# ATmega328P_MCU.net
KiCad netlist of a schematic drawn in EAGLE
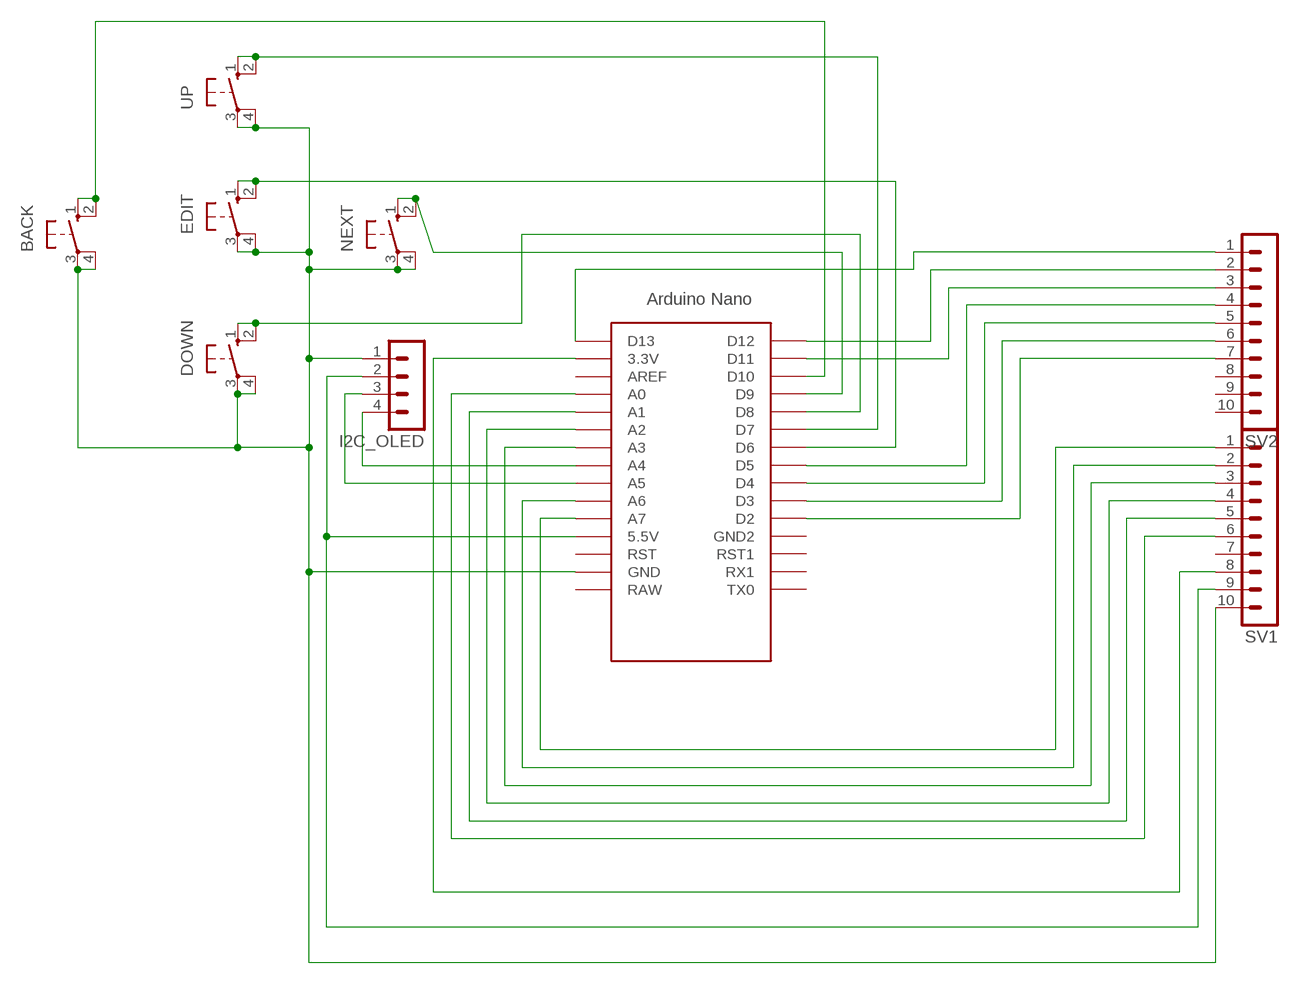
[diagram p0: schematic, sheet 1]

(export (version "E")
  (design (tool "Eeschema 10.0.6"))
  (components
    (comp (ref "ARDUINO")
      (value "NANO")
      (footprint "eagle-import:NANO")
      (libsource (lib "eagle-import") (part "NANO"))
    )
    (comp (ref "BACK")
      (value "10-XX")
      (footprint "eagle-import:B3F-10XX")
      (fields (field (name "MPN") "B3F-1000"))
      (libsource (lib "eagle-import") (part "10-XX"))
    )
    (comp (ref "DOWN")
      (value "10-XX")
      (footprint "eagle-import:B3F-10XX")
      (fields (field (name "MPN") "B3F-1000"))
      (libsource (lib "eagle-import") (part "10-XX"))
    )
    (comp (ref "EDIT")
      (value "10-XX")
      (footprint "eagle-import:B3F-10XX")
      (fields (field (name "MPN") "B3F-1000"))
      (libsource (lib "eagle-import") (part "10-XX"))
    )
    (comp (ref "I2C_OLED")
      (value "MA04-1")
      (footprint "eagle-import:MA04-1")
      (libsource (lib "eagle-import") (part "MA04-1"))
    )
    (comp (ref "NEXT")
      (value "10-XX")
      (footprint "eagle-import:B3F-10XX")
      (fields (field (name "MPN") "B3F-1000"))
      (libsource (lib "eagle-import") (part "10-XX"))
    )
    (comp (ref "SV1")
      (value "MA10-1")
      (footprint "eagle-import:MA10-1")
      (libsource (lib "eagle-import") (part "MA10-1"))
    )
    (comp (ref "SV2")
      (value "MA10-1")
      (footprint "eagle-import:MA10-1")
      (libsource (lib "eagle-import") (part "MA10-1"))
    )
    (comp (ref "UP")
      (value "10-XX")
      (footprint "eagle-import:B3F-10XX")
      (fields (field (name "MPN") "B3F-1000"))
      (libsource (lib "eagle-import") (part "10-XX"))
    )
  )
  (nets
    (net (code "1") (name "Net-(ARDUINO-5.5V)") (class "Default")
      (node (ref "ARDUINO") (pin "5V") (pinfunction "5.5V_5V") (pintype "bidirectional"))
      (node (ref "I2C_OLED") (pin "2") (pinfunction "2_2") (pintype "passive"))
      (node (ref "SV1") (pin "9") (pinfunction "9_9") (pintype "passive"))
    )
    (net (code "2") (name "Net-(ARDUINO-Pad3.3V)") (class "Default")
      (node (ref "ARDUINO") (pin "3.3V") (pinfunction "3.3V_3.3V") (pintype "bidirectional"))
      (node (ref "SV1") (pin "8") (pinfunction "8_8") (pintype "passive"))
    )
    (net (code "3") (name "Net-(ARDUINO-PadA0)") (class "Default")
      (node (ref "ARDUINO") (pin "A0") (pinfunction "A0_A0") (pintype "bidirectional"))
      (node (ref "SV1") (pin "6") (pinfunction "6_6") (pintype "passive"))
    )
    (net (code "4") (name "Net-(ARDUINO-PadA1)") (class "Default")
      (node (ref "ARDUINO") (pin "A1") (pinfunction "A1_A1") (pintype "bidirectional"))
      (node (ref "SV1") (pin "5") (pinfunction "5_5") (pintype "passive"))
    )
    (net (code "5") (name "Net-(ARDUINO-PadA2)") (class "Default")
      (node (ref "ARDUINO") (pin "A2") (pinfunction "A2_A2") (pintype "bidirectional"))
      (node (ref "SV1") (pin "4") (pinfunction "4_4") (pintype "passive"))
    )
    (net (code "6") (name "Net-(ARDUINO-PadA3)") (class "Default")
      (node (ref "ARDUINO") (pin "A3") (pinfunction "A3_A3") (pintype "bidirectional"))
      (node (ref "SV1") (pin "3") (pinfunction "3_3") (pintype "passive"))
    )
    (net (code "7") (name "Net-(ARDUINO-PadA4)") (class "Default")
      (node (ref "ARDUINO") (pin "A4") (pinfunction "A4_A4") (pintype "bidirectional"))
      (node (ref "I2C_OLED") (pin "4") (pinfunction "4_4") (pintype "passive"))
    )
    (net (code "8") (name "Net-(ARDUINO-PadA5)") (class "Default")
      (node (ref "ARDUINO") (pin "A5") (pinfunction "A5_A5") (pintype "bidirectional"))
      (node (ref "I2C_OLED") (pin "3") (pinfunction "3_3") (pintype "passive"))
    )
    (net (code "9") (name "Net-(ARDUINO-PadA6)") (class "Default")
      (node (ref "ARDUINO") (pin "A6") (pinfunction "A6_A6") (pintype "bidirectional"))
      (node (ref "SV1") (pin "2") (pinfunction "2_2") (pintype "passive"))
    )
    (net (code "10") (name "Net-(ARDUINO-PadA7)") (class "Default")
      (node (ref "ARDUINO") (pin "A7") (pinfunction "A7_A7") (pintype "bidirectional"))
      (node (ref "SV1") (pin "1") (pinfunction "1_1") (pintype "passive"))
    )
    (net (code "11") (name "Net-(ARDUINO-PadD2)") (class "Default")
      (node (ref "ARDUINO") (pin "D2") (pinfunction "D2_D2") (pintype "bidirectional"))
      (node (ref "SV2") (pin "7") (pinfunction "7_7") (pintype "passive"))
    )
    (net (code "12") (name "Net-(ARDUINO-PadD3)") (class "Default")
      (node (ref "ARDUINO") (pin "D3") (pinfunction "D3_D3") (pintype "bidirectional"))
      (node (ref "SV2") (pin "6") (pinfunction "6_6") (pintype "passive"))
    )
    (net (code "13") (name "Net-(ARDUINO-PadD4)") (class "Default")
      (node (ref "ARDUINO") (pin "D4") (pinfunction "D4_D4") (pintype "bidirectional"))
      (node (ref "SV2") (pin "5") (pinfunction "5_5") (pintype "passive"))
    )
    (net (code "14") (name "Net-(ARDUINO-PadD5)") (class "Default")
      (node (ref "ARDUINO") (pin "D5") (pinfunction "D5_D5") (pintype "bidirectional"))
      (node (ref "SV2") (pin "4") (pinfunction "4_4") (pintype "passive"))
    )
    (net (code "15") (name "Net-(ARDUINO-PadD11)") (class "Default")
      (node (ref "ARDUINO") (pin "D11") (pinfunction "D11_D11") (pintype "bidirectional"))
      (node (ref "SV2") (pin "3") (pinfunction "3_3") (pintype "passive"))
    )
    (net (code "16") (name "Net-(ARDUINO-PadD12)") (class "Default")
      (node (ref "ARDUINO") (pin "D12") (pinfunction "D12_D12") (pintype "bidirectional"))
      (node (ref "SV2") (pin "2") (pinfunction "2_2") (pintype "passive"))
    )
    (net (code "17") (name "Net-(ARDUINO-PadD13)") (class "Default")
      (node (ref "ARDUINO") (pin "D13") (pinfunction "D13_D13") (pintype "bidirectional"))
      (node (ref "SV2") (pin "1") (pinfunction "1_1") (pintype "passive"))
    )
    (net (code "18") (name "Net-(BACK-P)") (class "Default")
      (node (ref "ARDUINO") (pin "GND") (pinfunction "GND_GND") (pintype "bidirectional"))
      (node (ref "BACK") (pin "3") (pinfunction "P_3") (pintype "passive"))
      (node (ref "BACK") (pin "4") (pinfunction "P1_4") (pintype "passive"))
      (node (ref "DOWN") (pin "3") (pinfunction "P_3") (pintype "passive"))
      (node (ref "DOWN") (pin "4") (pinfunction "P1_4") (pintype "passive"))
      (node (ref "EDIT") (pin "3") (pinfunction "P_3") (pintype "passive"))
      (node (ref "EDIT") (pin "4") (pinfunction "P1_4") (pintype "passive"))
      (node (ref "I2C_OLED") (pin "1") (pinfunction "1_1") (pintype "passive"))
      (node (ref "NEXT") (pin "3") (pinfunction "P_3") (pintype "passive"))
      (node (ref "NEXT") (pin "4") (pinfunction "P1_4") (pintype "passive"))
      (node (ref "SV1") (pin "10") (pinfunction "10_10") (pintype "passive"))
      (node (ref "UP") (pin "3") (pinfunction "P_3") (pintype "passive"))
      (node (ref "UP") (pin "4") (pinfunction "P1_4") (pintype "passive"))
    )
    (net (code "19") (name "Net-(BACK-S)") (class "Default")
      (node (ref "ARDUINO") (pin "D10") (pinfunction "D10_D10") (pintype "bidirectional"))
      (node (ref "BACK") (pin "1") (pinfunction "S_1") (pintype "passive"))
      (node (ref "BACK") (pin "2") (pinfunction "S1_2") (pintype "passive"))
    )
    (net (code "20") (name "Net-(DOWN-S)") (class "Default")
      (node (ref "ARDUINO") (pin "D8") (pinfunction "D8_D8") (pintype "bidirectional"))
      (node (ref "DOWN") (pin "1") (pinfunction "S_1") (pintype "passive"))
      (node (ref "DOWN") (pin "2") (pinfunction "S1_2") (pintype "passive"))
    )
    (net (code "21") (name "Net-(EDIT-S)") (class "Default")
      (node (ref "ARDUINO") (pin "D6") (pinfunction "D6_D6") (pintype "bidirectional"))
      (node (ref "EDIT") (pin "1") (pinfunction "S_1") (pintype "passive"))
      (node (ref "EDIT") (pin "2") (pinfunction "S1_2") (pintype "passive"))
    )
    (net (code "22") (name "Net-(NEXT-S)") (class "Default")
      (node (ref "ARDUINO") (pin "D9") (pinfunction "D9_D9") (pintype "bidirectional"))
      (node (ref "NEXT") (pin "1") (pinfunction "S_1") (pintype "passive"))
      (node (ref "NEXT") (pin "2") (pinfunction "S1_2") (pintype "passive"))
    )
    (net (code "23") (name "Net-(UP-S)") (class "Default")
      (node (ref "ARDUINO") (pin "D7") (pinfunction "D7_D7") (pintype "bidirectional"))
      (node (ref "UP") (pin "1") (pinfunction "S_1") (pintype "passive"))
      (node (ref "UP") (pin "2") (pinfunction "S1_2") (pintype "passive"))
    )
    (net (code "24") (name "unconnected-(ARDUINO-GND2-PadGND1)") (class "Default")
      (node (ref "ARDUINO") (pin "GND1") (pinfunction "GND2_GND1") (pintype "bidirectional"))
    )
    (net (code "25") (name "unconnected-(ARDUINO-PadAREF)") (class "Default")
      (node (ref "ARDUINO") (pin "AREF") (pinfunction "AREF_AREF") (pintype "bidirectional"))
    )
    (net (code "26") (name "unconnected-(ARDUINO-PadRAW)") (class "Default")
      (node (ref "ARDUINO") (pin "RAW") (pinfunction "RAW_RAW") (pintype "bidirectional"))
    )
    (net (code "27") (name "unconnected-(ARDUINO-PadRST)") (class "Default")
      (node (ref "ARDUINO") (pin "RST") (pinfunction "RST_RST") (pintype "bidirectional"))
    )
    (net (code "28") (name "unconnected-(ARDUINO-PadRST1)") (class "Default")
      (node (ref "ARDUINO") (pin "RST1") (pinfunction "RST1_RST1") (pintype "bidirectional"))
    )
    (net (code "29") (name "unconnected-(ARDUINO-PadRX1)") (class "Default")
      (node (ref "ARDUINO") (pin "RX1") (pinfunction "RX1_RX1") (pintype "bidirectional"))
    )
    (net (code "30") (name "unconnected-(ARDUINO-PadTX0)") (class "Default")
      (node (ref "ARDUINO") (pin "TX0") (pinfunction "TX0_TX0") (pintype "bidirectional"))
    )
    (net (code "31") (name "unconnected-(SV1-Pad7)") (class "Default")
      (node (ref "SV1") (pin "7") (pinfunction "7_7") (pintype "passive"))
    )
    (net (code "32") (name "unconnected-(SV2-Pad8)") (class "Default")
      (node (ref "SV2") (pin "8") (pinfunction "8_8") (pintype "passive"))
    )
    (net (code "33") (name "unconnected-(SV2-Pad9)") (class "Default")
      (node (ref "SV2") (pin "9") (pinfunction "9_9") (pintype "passive"))
    )
    (net (code "34") (name "unconnected-(SV2-Pad10)") (class "Default")
      (node (ref "SV2") (pin "10") (pinfunction "10_10") (pintype "passive"))
    )
  )
)
